# obc_main_3_0.net
KiCad netlist of a schematic drawn in Altium Designer
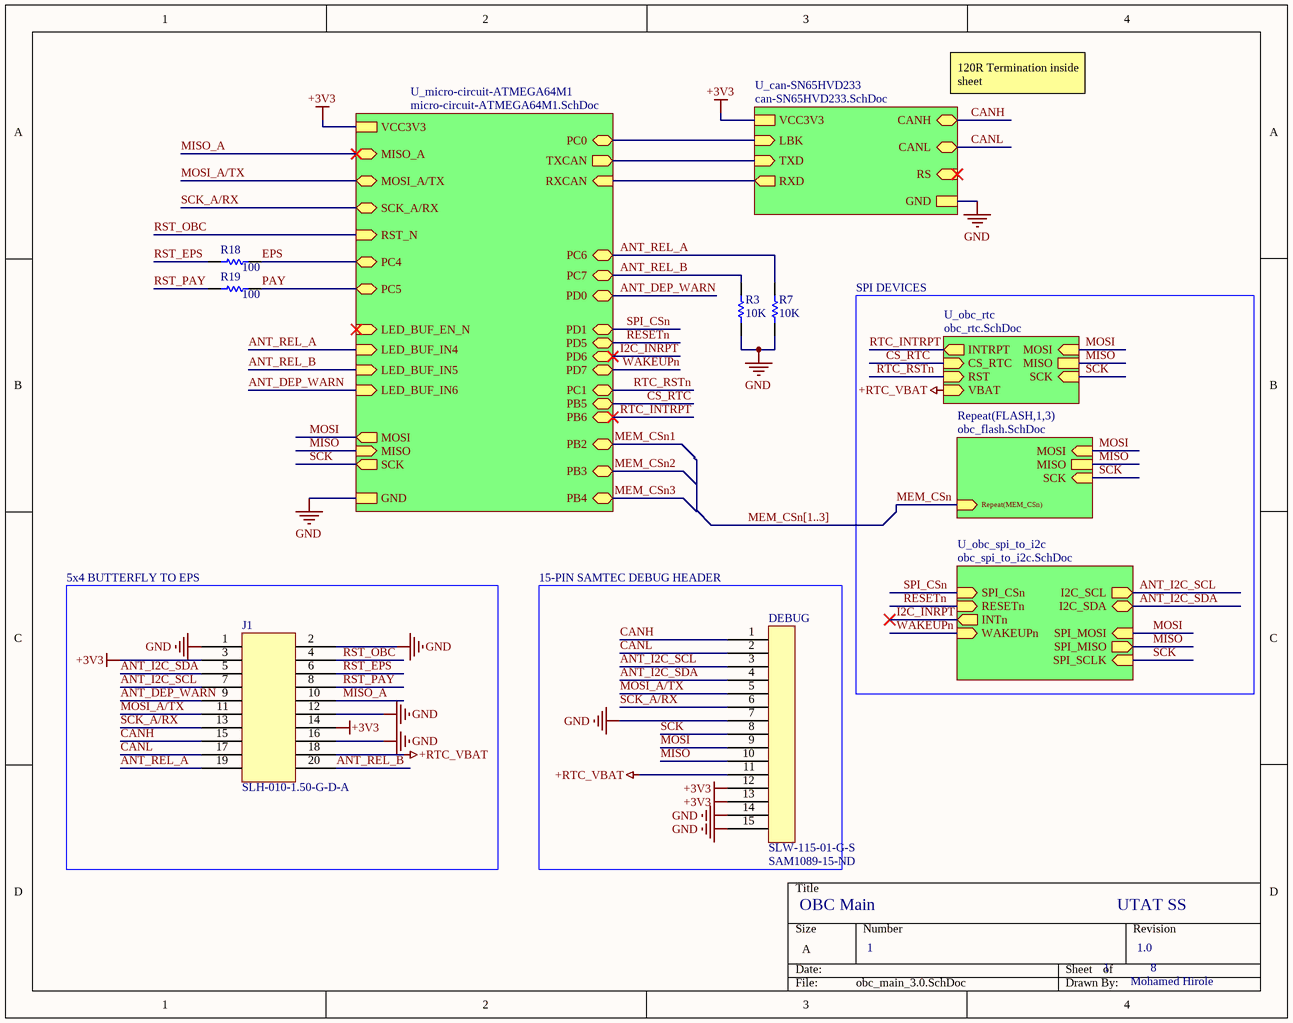
[diagram p0: obc_main_3.0.SchDoc]

(export (version "E")
  (design (tool "Eeschema 10.0.6"))
  (components
    (comp (ref "DEBUG")
      (value "SLW-115-01-G-S")
      (footprint "SAM1089-15-ND")
      (description "15 Position Receptacle Connector 0.100\" (2.54mm) Through Hole Gold")
      (fields (field (name "MANUFACTURER") "Samtec") (field (name "SUPPLIER PART NUMBER 1") "SAM1089-15-ND"))
      (libsource (lib "heron-general") (part "SLW-115-01-G-S"))
    )
    (comp (ref "J1")
      (value "SLH-010-1.50-G-D-A")
      (footprint "SLH-010-1.50-G-D-A")
      (description "0.50 mm Razor Beam™ LP Ultra Low Profile Socket Strip, alignment pin option")
      (libsource (lib "heron-general") (part "SLH-010-1.50-G-D-A"))
    )
    (comp (ref "R3")
      (value "10K")
      (footprint "RES0603R")
      (description "0603 resistor")
      (fields (field (name "Comment") "0603"))
      (libsource (lib "heron-general") (part "RES0603"))
    )
    (comp (ref "R7")
      (value "10K")
      (footprint "RES0603R")
      (description "0603 resistor")
      (fields (field (name "Comment") "0603"))
      (libsource (lib "heron-general") (part "RES0603"))
    )
    (comp (ref "R18")
      (value "100")
      (footprint "RES0603R")
      (description "0603 resistor")
      (fields (field (name "Comment") "0603"))
      (libsource (lib "heron-general") (part "RES0603"))
    )
    (comp (ref "R19")
      (value "100")
      (footprint "RES0603R")
      (description "0603 resistor")
      (fields (field (name "Comment") "0603"))
      (libsource (lib "heron-general") (part "RES0603"))
    )
  )
  (nets
    (net (code "1") (name "+3V3") (class "Default")
      (node (ref "DEBUG") (pin "12") (pintype "passive"))
      (node (ref "DEBUG") (pin "13") (pintype "passive"))
      (node (ref "J1") (pin "14") (pintype "passive"))
      (node (ref "J1") (pin "3") (pintype "passive"))
    )
    (net (code "2") (name "+RTC_VBAT") (class "Default")
      (node (ref "DEBUG") (pin "11") (pintype "passive"))
      (node (ref "J1") (pin "18") (pintype "passive"))
    )
    (net (code "3") (name "/ANT_DEP_WARN") (class "Default") (node (ref "J1") (pin "9") (pintype "passive")))
    (net (code "4") (name "/ANT_I2C_SCL") (class "Default")
      (node (ref "DEBUG") (pin "3") (pintype "passive"))
      (node (ref "J1") (pin "7") (pintype "passive"))
    )
    (net (code "5") (name "/ANT_I2C_SDA") (class "Default")
      (node (ref "DEBUG") (pin "4") (pintype "passive"))
      (node (ref "J1") (pin "5") (pintype "passive"))
    )
    (net (code "6") (name "/ANT_REL_A") (class "Default")
      (node (ref "J1") (pin "19") (pintype "passive"))
      (node (ref "R7") (pin "2") (pinfunction "2_2") (pintype "passive"))
    )
    (net (code "7") (name "/ANT_REL_B") (class "Default")
      (node (ref "J1") (pin "20") (pintype "passive"))
      (node (ref "R3") (pin "2") (pinfunction "2_2") (pintype "passive"))
    )
    (net (code "8") (name "/CANH") (class "Default")
      (node (ref "DEBUG") (pin "1") (pintype "passive"))
      (node (ref "J1") (pin "15") (pintype "passive"))
    )
    (net (code "9") (name "/CANL") (class "Default")
      (node (ref "DEBUG") (pin "2") (pintype "passive"))
      (node (ref "J1") (pin "17") (pintype "passive"))
    )
    (net (code "11") (name "/EPS") (class "Default")
      (node (ref "R18") (pin "2") (pinfunction "2_2") (pintype "passive"))
    )
    (net (code "20") (name "/MISO") (class "Default") (node (ref "DEBUG") (pin "10") (pintype "passive")))
    (net (code "21") (name "/MISO_A") (class "Default") (node (ref "J1") (pin "10") (pintype "passive")))
    (net (code "22") (name "/MOSI") (class "Default") (node (ref "DEBUG") (pin "9") (pintype "passive")))
    (net (code "23") (name "/MOSI_A{slash}TX") (class "Default")
      (node (ref "DEBUG") (pin "5") (pintype "passive"))
      (node (ref "J1") (pin "11") (pintype "passive"))
    )
    (net (code "24") (name "/PAY") (class "Default")
      (node (ref "R19") (pin "2") (pinfunction "2_2") (pintype "passive"))
    )
    (net (code "27") (name "/RST_EPS") (class "Default")
      (node (ref "J1") (pin "6") (pintype "passive"))
      (node (ref "R18") (pin "1") (pinfunction "1_1") (pintype "passive"))
    )
    (net (code "28") (name "/RST_OBC") (class "Default") (node (ref "J1") (pin "4") (pintype "passive")))
    (net (code "29") (name "/RST_PAY") (class "Default")
      (node (ref "J1") (pin "8") (pintype "passive"))
      (node (ref "R19") (pin "1") (pinfunction "1_1") (pintype "passive"))
    )
    (net (code "33") (name "/SCK") (class "Default") (node (ref "DEBUG") (pin "8") (pintype "passive")))
    (net (code "34") (name "/SCK_A{slash}RX") (class "Default")
      (node (ref "DEBUG") (pin "6") (pintype "passive"))
      (node (ref "J1") (pin "13") (pintype "passive"))
    )
    (net (code "38") (name "GND") (class "Default")
      (node (ref "DEBUG") (pin "14") (pintype "passive"))
      (node (ref "DEBUG") (pin "15") (pintype "passive"))
      (node (ref "DEBUG") (pin "7") (pintype "passive"))
      (node (ref "J1") (pin "1") (pintype "passive"))
      (node (ref "J1") (pin "12") (pintype "passive"))
      (node (ref "J1") (pin "16") (pintype "passive"))
      (node (ref "J1") (pin "2") (pintype "passive"))
      (node (ref "R3") (pin "1") (pinfunction "1_1") (pintype "passive"))
      (node (ref "R7") (pin "1") (pinfunction "1_1") (pintype "passive"))
    )
  )
)
